# TSALsch.net
KiCad netlist of a schematic drawn in Altium Designer
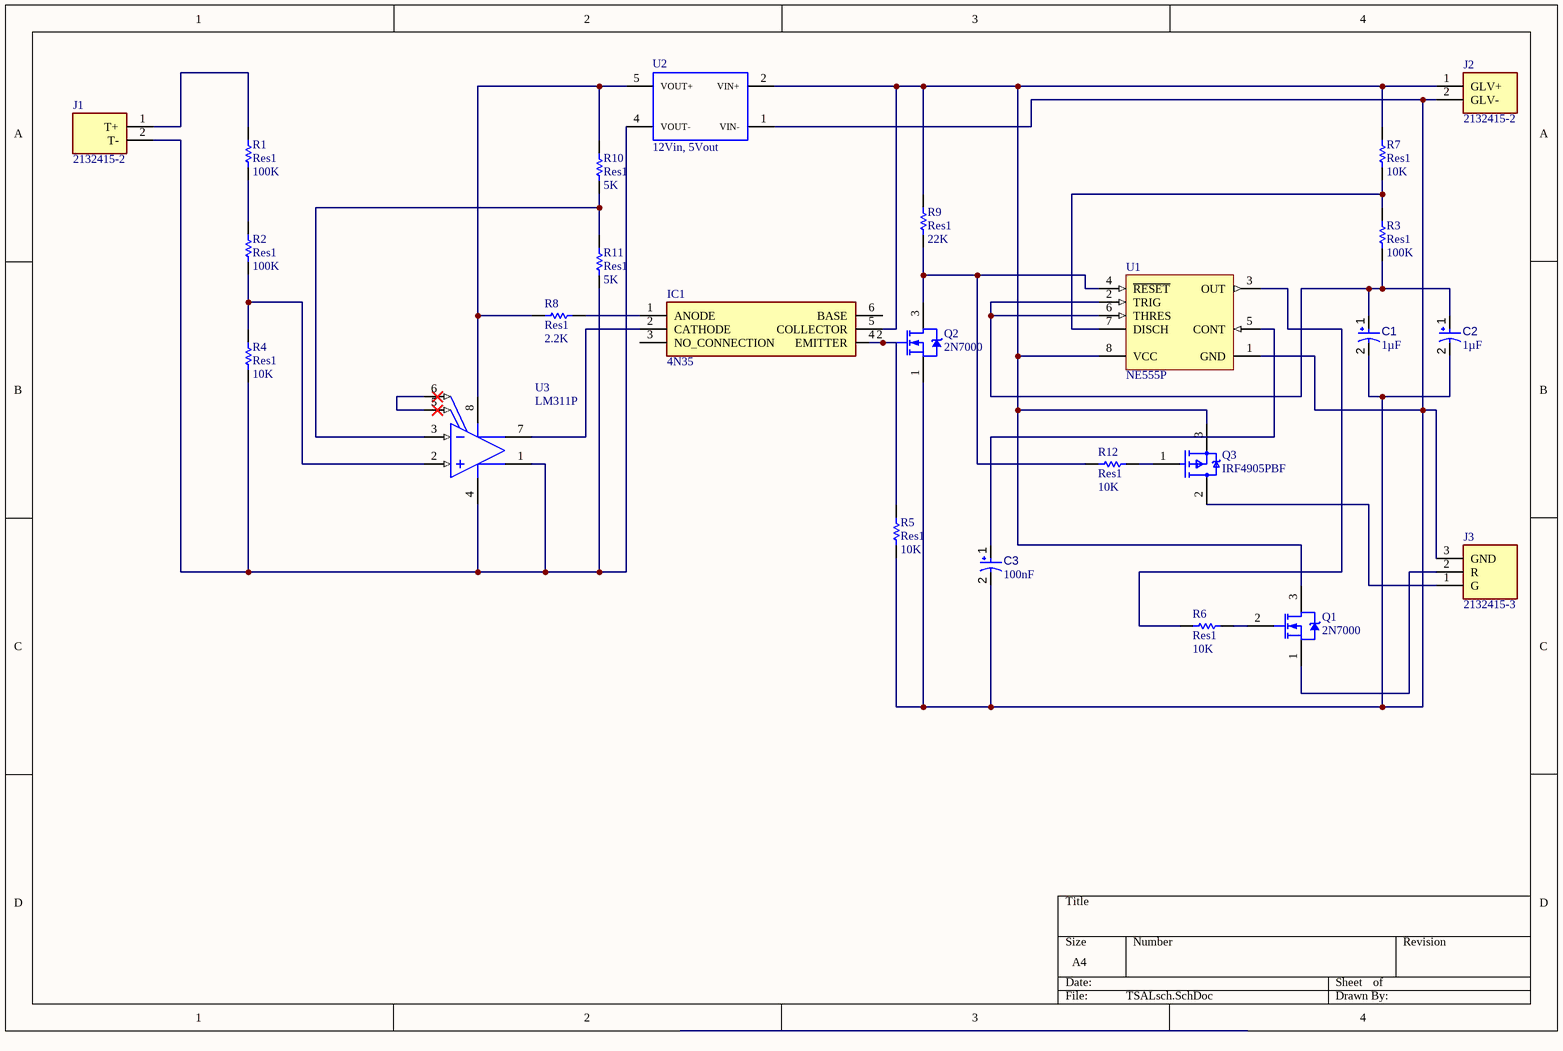
[diagram p0: TSALsch.SchDoc]

(export (version "E")
  (design (tool "Eeschema 10.0.6"))
  (components
    (comp (ref "C1")
      (value "1µF")
      (footprint "CAPPR55-250-1120X630X1220")
      (description "Aluminum Electrolytic Capacitor, 47 uF, +/-20%, 50 V, -40 to 85 degC, 2-Pin THD, RoHS, Bulk")
      (fields (field (name "MANUFACTURER") "Panasonic") (field (name "TOLERANCE") "20%"))
      (libsource (lib "Team Solarium Energy Circuits") (part "CAP-P-2"))
    )
    (comp (ref "C2")
      (value "1µF")
      (footprint "CAPPR55-250-1120X630X1220")
      (description "Aluminum Electrolytic Capacitor, 47 uF, +/-20%, 50 V, -40 to 85 degC, 2-Pin THD, RoHS, Bulk")
      (fields (field (name "MANUFACTURER") "Panasonic") (field (name "TOLERANCE") "20%"))
      (libsource (lib "Team Solarium Energy Circuits") (part "CAP-P-2"))
    )
    (comp (ref "C3")
      (value "100nF")
      (footprint "CAPPR55-250-1120X630X1220")
      (description "Aluminum Electrolytic Capacitor, 47 uF, +/-20%, 50 V, -40 to 85 degC, 2-Pin THD, RoHS, Bulk")
      (fields (field (name "MANUFACTURER") "Panasonic") (field (name "TOLERANCE") "20%"))
      (libsource (lib "Team Solarium Energy Circuits") (part "CAP-P-2"))
    )
    (comp (ref "IC1")
      (value "4N35")
      (footprint "SamacSys:DIP762W56P254L864H508Q6N")
      (description "Integrated Circuit")
      (fields (field (name "MOUSER PART NUMBER") "512-4N35"))
      (libsource (lib "*") (part "4N35"))
    )
    (comp (ref "J1")
      (value "2132415-2")
      (footprint "TE_2132415-2")
      (description "Conn Shrouded Header HDR 2 POS 2.5mm Solder ST Thru-Hole Bag/Box")
      (fields (field (name "DIGI-KEY_PART_NUMBER") "A101065-ND") (field (name "MF") "TE Connectivity"))
      (libsource (lib "2132415-2") (part "2132415-2"))
    )
    (comp (ref "J2")
      (value "2132415-2")
      (footprint "TE_2132415-2")
      (description "Conn Shrouded Header HDR 2 POS 2.5mm Solder ST Thru-Hole Bag/Box")
      (fields (field (name "DIGI-KEY_PART_NUMBER") "A101065-ND") (field (name "MF") "TE Connectivity"))
      (libsource (lib "") (part "2132415-2_1"))
    )
    (comp (ref "J3")
      (value "2132415-3")
      (footprint "TE_2132415-3")
      (description "Conn Shrouded Header HDR 3 POS 2.5mm Solder ST Thru-Hole Bag/Box")
      (fields (field (name "MF") "TE Connectivity"))
      (libsource (lib "2132415-3") (part "2132415-3"))
    )
    (comp (ref "Q1")
      (value "2N7000")
      (footprint "ONSC-TO-92-3-29-11_AM_BL")
      (description "Small Signal MOSFET, 200 mA, 60 V, N-Channel, 3-Pin TO-92, Bulk Box")
      (fields (field (name "MANUFACTURER") "Fairchild Semiconductor") (field (name "POWER") "400mW"))
      (libsource (lib "Team Solarium Energy Circuits") (part "ONSC-NMOS-S1G2D3-3"))
    )
    (comp (ref "Q2")
      (value "2N7000")
      (footprint "ONSC-TO-92-3-29-11_AM_BL")
      (description "Small Signal MOSFET, 200 mA, 60 V, N-Channel, 3-Pin TO-92, Bulk Box")
      (fields (field (name "MANUFACTURER") "Fairchild Semiconductor") (field (name "POWER") "400mW"))
      (libsource (lib "Team Solarium Energy Circuits") (part "ONSC-NMOS-S1G2D3-3"))
    )
    (comp (ref "Q3")
      (value "IRF4905PBF")
      (footprint "FP-PG-TO220-3-MFG")
      (description "MOSFET P-CH 55V 74A TO-220AB")
      (libsource (lib "Altium Content Vault") (part "7c43f5ccbd0f8ca8bbf61673af0f16f"))
    )
    (comp (ref "R1")
      (value "Res1")
      (footprint "AXIAL-0.3")
      (description "Resistor")
      (fields (field (name "ALTIUM_VALUE") "100K") (field (name "PUBLISHER") "Altium Limited"))
      (libsource (lib "Miscellaneous Devices") (part "Res1"))
    )
    (comp (ref "R2")
      (value "Res1")
      (footprint "AXIAL-0.3")
      (description "Resistor")
      (fields (field (name "ALTIUM_VALUE") "100K") (field (name "PUBLISHER") "Altium Limited"))
      (libsource (lib "Miscellaneous Devices") (part "Res1"))
    )
    (comp (ref "R3")
      (value "Res1")
      (footprint "AXIAL-0.3")
      (description "Resistor")
      (fields (field (name "ALTIUM_VALUE") "100K") (field (name "PUBLISHER") "Altium Limited"))
      (libsource (lib "Miscellaneous Devices") (part "Res1"))
    )
    (comp (ref "R4")
      (value "Res1")
      (footprint "AXIAL-0.3")
      (description "Resistor")
      (fields (field (name "ALTIUM_VALUE") "10K") (field (name "PUBLISHER") "Altium Limited"))
      (libsource (lib "Miscellaneous Devices") (part "Res1"))
    )
    (comp (ref "R5")
      (value "Res1")
      (footprint "AXIAL-0.3")
      (description "Resistor")
      (fields (field (name "ALTIUM_VALUE") "10K") (field (name "PUBLISHER") "Altium Limited"))
      (libsource (lib "Miscellaneous Devices") (part "Res1"))
    )
    (comp (ref "R6")
      (value "Res1")
      (footprint "AXIAL-0.3")
      (description "Resistor")
      (fields (field (name "ALTIUM_VALUE") "10K") (field (name "PUBLISHER") "Altium Limited"))
      (libsource (lib "Miscellaneous Devices") (part "Res1"))
    )
    (comp (ref "R7")
      (value "Res1")
      (footprint "AXIAL-0.3")
      (description "Resistor")
      (fields (field (name "ALTIUM_VALUE") "10K") (field (name "PUBLISHER") "Altium Limited"))
      (libsource (lib "Miscellaneous Devices") (part "Res1"))
    )
    (comp (ref "R8")
      (value "Res1")
      (footprint "AXIAL-0.3")
      (description "Resistor")
      (fields (field (name "ALTIUM_VALUE") "2.2K") (field (name "PUBLISHER") "Altium Limited"))
      (libsource (lib "Miscellaneous Devices") (part "Res1"))
    )
    (comp (ref "R9")
      (value "Res1")
      (footprint "AXIAL-0.3")
      (description "Resistor")
      (fields (field (name "ALTIUM_VALUE") "22K") (field (name "PUBLISHER") "Altium Limited"))
      (libsource (lib "Miscellaneous Devices") (part "Res1"))
    )
    (comp (ref "R10")
      (value "Res1")
      (footprint "AXIAL-0.3")
      (description "Resistor")
      (fields (field (name "ALTIUM_VALUE") "5K") (field (name "PUBLISHER") "Altium Limited"))
      (libsource (lib "Miscellaneous Devices") (part "Res1"))
    )
    (comp (ref "R11")
      (value "Res1")
      (footprint "AXIAL-0.3")
      (description "Resistor")
      (fields (field (name "ALTIUM_VALUE") "5K") (field (name "PUBLISHER") "Altium Limited"))
      (libsource (lib "Miscellaneous Devices") (part "Res1"))
    )
    (comp (ref "R12")
      (value "Res1")
      (footprint "AXIAL-0.3")
      (description "Resistor")
      (fields (field (name "ALTIUM_VALUE") "10K") (field (name "PUBLISHER") "Altium Limited"))
      (libsource (lib "Miscellaneous Devices") (part "Res1"))
    )
    (comp (ref "U1")
      (value "NE555P")
      (footprint "P0008A")
      (description "Precision Timer, 4.5 to 16 V, 0 to 70 degC, 8-Pin DIP, Pb-Free, Tube")
      (fields (field (name "MANUFACTURER") "TexasInstruments"))
      (libsource (lib "Altium Content Vault") (part "TI-NE555-P8"))
    )
    (comp (ref "U2")
      (value "12Vin, 5Vout")
      (footprint "SMT-8")
      (description "MagI3C-FISM Fixed Isolated SIP Module, SMT-8, 12Vin, 5Vout")
      (fields (field (name "PART NUMBER") "176920522") (field (name "PUBLISHER") "Wurth Elektronik"))
      (libsource (lib "Altium_MagI3C-FISM (rev19a)") (part "176920522"))
    )
    (comp (ref "U3")
      (value "LM311P")
      (footprint "P0008A")
      (description "Quad Differential Comparator, 3.5 to 30 V, 0 to 70 degC, 8-Pin PDIP (P), Pb-Free (RoHS), Tube")
      (fields (field (name "MANUFACTURER") "Texas Instruments (TI)"))
      (libsource (lib "Team Solarium Energy Circuits") (part "TI-LXX11-8"))
    )
  )
  (nets
    (net (code "1") (name "Net-(IC1-ANODE)") (class "Default")
      (node (ref "IC1") (pin "1") (pinfunction "ANODE_1") (pintype "passive"))
      (node (ref "R8") (pin "2") (pinfunction "2_2") (pintype "passive"))
    )
    (net (code "2") (name "Net-(IC1-CATHODE)") (class "Default")
      (node (ref "IC1") (pin "2") (pinfunction "CATHODE_2") (pintype "passive"))
      (node (ref "U3") (pin "7") (pinfunction "COL_OUT_7") (pintype "passive"))
    )
    (net (code "3") (name "Net-(IC1-COLLECTOR)") (class "Default")
      (node (ref "IC1") (pin "5") (pinfunction "COLLECTOR_5") (pintype "passive"))
      (node (ref "J2") (pin "1") (pinfunction "GLV+_1") (pintype "passive"))
      (node (ref "Q1") (pin "3") (pinfunction "D_3") (pintype "passive"))
      (node (ref "Q3") (pin "3") (pinfunction "SOURCE_3") (pintype "passive"))
      (node (ref "R7") (pin "2") (pinfunction "2_2") (pintype "passive"))
      (node (ref "R9") (pin "2") (pinfunction "2_2") (pintype "passive"))
      (node (ref "U1") (pin "8") (pinfunction "VCC_8") (pintype "power_in"))
      (node (ref "U2") (pin "2") (pinfunction "VIN+_2") (pintype "passive"))
    )
    (net (code "4") (name "Net-(IC1-EMITTER)") (class "Default")
      (node (ref "IC1") (pin "4") (pinfunction "EMITTER_4") (pintype "passive"))
      (node (ref "Q2") (pin "2") (pinfunction "G_2") (pintype "passive"))
      (node (ref "R5") (pin "2") (pinfunction "2_2") (pintype "passive"))
    )
    (net (code "5") (name "Net-(J1-T+)") (class "Default")
      (node (ref "J1") (pin "1") (pinfunction "T+_1") (pintype "passive"))
      (node (ref "R1") (pin "2") (pinfunction "2_2") (pintype "passive"))
    )
    (net (code "6") (name "Net-(J1-T-)") (class "Default")
      (node (ref "J1") (pin "2") (pinfunction "T-_2") (pintype "passive"))
      (node (ref "R11") (pin "1") (pinfunction "1_1") (pintype "passive"))
      (node (ref "R4") (pin "1") (pinfunction "1_1") (pintype "passive"))
      (node (ref "U2") (pin "4") (pinfunction "VOUT-_4") (pintype "passive"))
      (node (ref "U3") (pin "1") (pinfunction "EMIT_OUT_1") (pintype "passive"))
      (node (ref "U3") (pin "4") (pinfunction "VCC-_4") (pintype "power_in"))
    )
    (net (code "7") (name "Net-(J2-GLV-)") (class "Default")
      (node (ref "C1") (pin "2") (pinfunction "2_2") (pintype "passive"))
      (node (ref "C2") (pin "2") (pinfunction "2_2") (pintype "passive"))
      (node (ref "C3") (pin "2") (pinfunction "2_2") (pintype "passive"))
      (node (ref "J2") (pin "2") (pinfunction "GLV-_2") (pintype "passive"))
      (node (ref "J3") (pin "3") (pinfunction "GND_3") (pintype "passive"))
      (node (ref "Q2") (pin "1") (pinfunction "S_1") (pintype "passive"))
      (node (ref "R5") (pin "1") (pinfunction "1_1") (pintype "passive"))
      (node (ref "U1") (pin "1") (pinfunction "GND_1") (pintype "power_in"))
      (node (ref "U2") (pin "1") (pinfunction "VIN-_1") (pintype "passive"))
    )
    (net (code "8") (name "Net-(J3-G)") (class "Default")
      (node (ref "J3") (pin "1") (pinfunction "G_1") (pintype "passive"))
      (node (ref "Q3") (pin "2") (pinfunction "DRAIN_2") (pintype "passive"))
    )
    (net (code "9") (name "Net-(J3-R)") (class "Default")
      (node (ref "J3") (pin "2") (pinfunction "R_2") (pintype "passive"))
      (node (ref "Q1") (pin "1") (pinfunction "S_1") (pintype "passive"))
    )
    (net (code "10") (name "Net-(Q1-G)") (class "Default")
      (node (ref "Q1") (pin "2") (pinfunction "G_2") (pintype "passive"))
      (node (ref "R6") (pin "2") (pinfunction "2_2") (pintype "passive"))
    )
    (net (code "11") (name "Net-(Q2-D)") (class "Default")
      (node (ref "Q2") (pin "3") (pinfunction "D_3") (pintype "passive"))
      (node (ref "R12") (pin "1") (pinfunction "1_1") (pintype "passive"))
      (node (ref "R9") (pin "1") (pinfunction "1_1") (pintype "passive"))
      (node (ref "U1") (pin "4") (pinfunction "~{RESET}_4") (pintype "input"))
    )
    (net (code "12") (name "Net-(Q3-GATE)") (class "Default")
      (node (ref "Q3") (pin "1") (pinfunction "GATE_1") (pintype "passive"))
      (node (ref "R12") (pin "2") (pinfunction "2_2") (pintype "passive"))
    )
    (net (code "13") (name "Net-(R1-Pad1)") (class "Default")
      (node (ref "R1") (pin "1") (pinfunction "1_1") (pintype "passive"))
      (node (ref "R2") (pin "2") (pinfunction "2_2") (pintype "passive"))
    )
    (net (code "14") (name "Net-(U1-CONT)") (class "Default")
      (node (ref "C3") (pin "1") (pinfunction "1_1") (pintype "passive"))
      (node (ref "U1") (pin "5") (pinfunction "CONT_5") (pintype "input"))
    )
    (net (code "15") (name "Net-(U1-DISCH)") (class "Default")
      (node (ref "R3") (pin "2") (pinfunction "2_2") (pintype "passive"))
      (node (ref "R7") (pin "1") (pinfunction "1_1") (pintype "passive"))
      (node (ref "U1") (pin "7") (pinfunction "DISCH_7") (pintype "open_collector"))
    )
    (net (code "16") (name "Net-(U1-OUT)") (class "Default")
      (node (ref "R6") (pin "1") (pinfunction "1_1") (pintype "passive"))
      (node (ref "U1") (pin "3") (pinfunction "OUT_3") (pintype "output"))
    )
    (net (code "17") (name "Net-(U1-THRES)") (class "Default")
      (node (ref "C1") (pin "1") (pinfunction "1_1") (pintype "passive"))
      (node (ref "C2") (pin "1") (pinfunction "1_1") (pintype "passive"))
      (node (ref "R3") (pin "1") (pinfunction "1_1") (pintype "passive"))
      (node (ref "U1") (pin "2") (pinfunction "TRIG_2") (pintype "input"))
      (node (ref "U1") (pin "6") (pinfunction "THRES_6") (pintype "input"))
    )
    (net (code "18") (name "Net-(U2-VOUT+)") (class "Default")
      (node (ref "R10") (pin "2") (pinfunction "2_2") (pintype "passive"))
      (node (ref "R8") (pin "1") (pinfunction "1_1") (pintype "passive"))
      (node (ref "U2") (pin "5") (pinfunction "VOUT+_5") (pintype "passive"))
      (node (ref "U3") (pin "8") (pinfunction "VCC+_8") (pintype "power_in"))
    )
    (net (code "19") (name "Net-(U3-BALANCE)") (class "Default")
      (node (ref "U3") (pin "5") (pinfunction "BALANCE_5") (pintype "input"))
      (node (ref "U3") (pin "6") (pinfunction "BAL/STRB_6") (pintype "input"))
    )
    (net (code "20") (name "Net-(U3-IN+)") (class "Default")
      (node (ref "R2") (pin "1") (pinfunction "1_1") (pintype "passive"))
      (node (ref "R4") (pin "2") (pinfunction "2_2") (pintype "passive"))
      (node (ref "U3") (pin "2") (pinfunction "IN+_2") (pintype "input"))
    )
    (net (code "21") (name "Net-(U3-IN-)") (class "Default")
      (node (ref "R10") (pin "1") (pinfunction "1_1") (pintype "passive"))
      (node (ref "R11") (pin "2") (pinfunction "2_2") (pintype "passive"))
      (node (ref "U3") (pin "3") (pinfunction "IN-_3") (pintype "input"))
    )
    (net (code "22") (name "unconnected-(IC1-BASE-Pad6)") (class "Default")
      (node (ref "IC1") (pin "6") (pinfunction "BASE_6") (pintype "passive"))
    )
    (net (code "23") (name "unconnected-(IC1-NO_CONNECTION-Pad3)") (class "Default")
      (node (ref "IC1") (pin "3") (pinfunction "NO_CONNECTION_3") (pintype "passive"))
    )
  )
)
